# BOB_v0_6.net
KiCad netlist of a schematic drawn in EAGLE
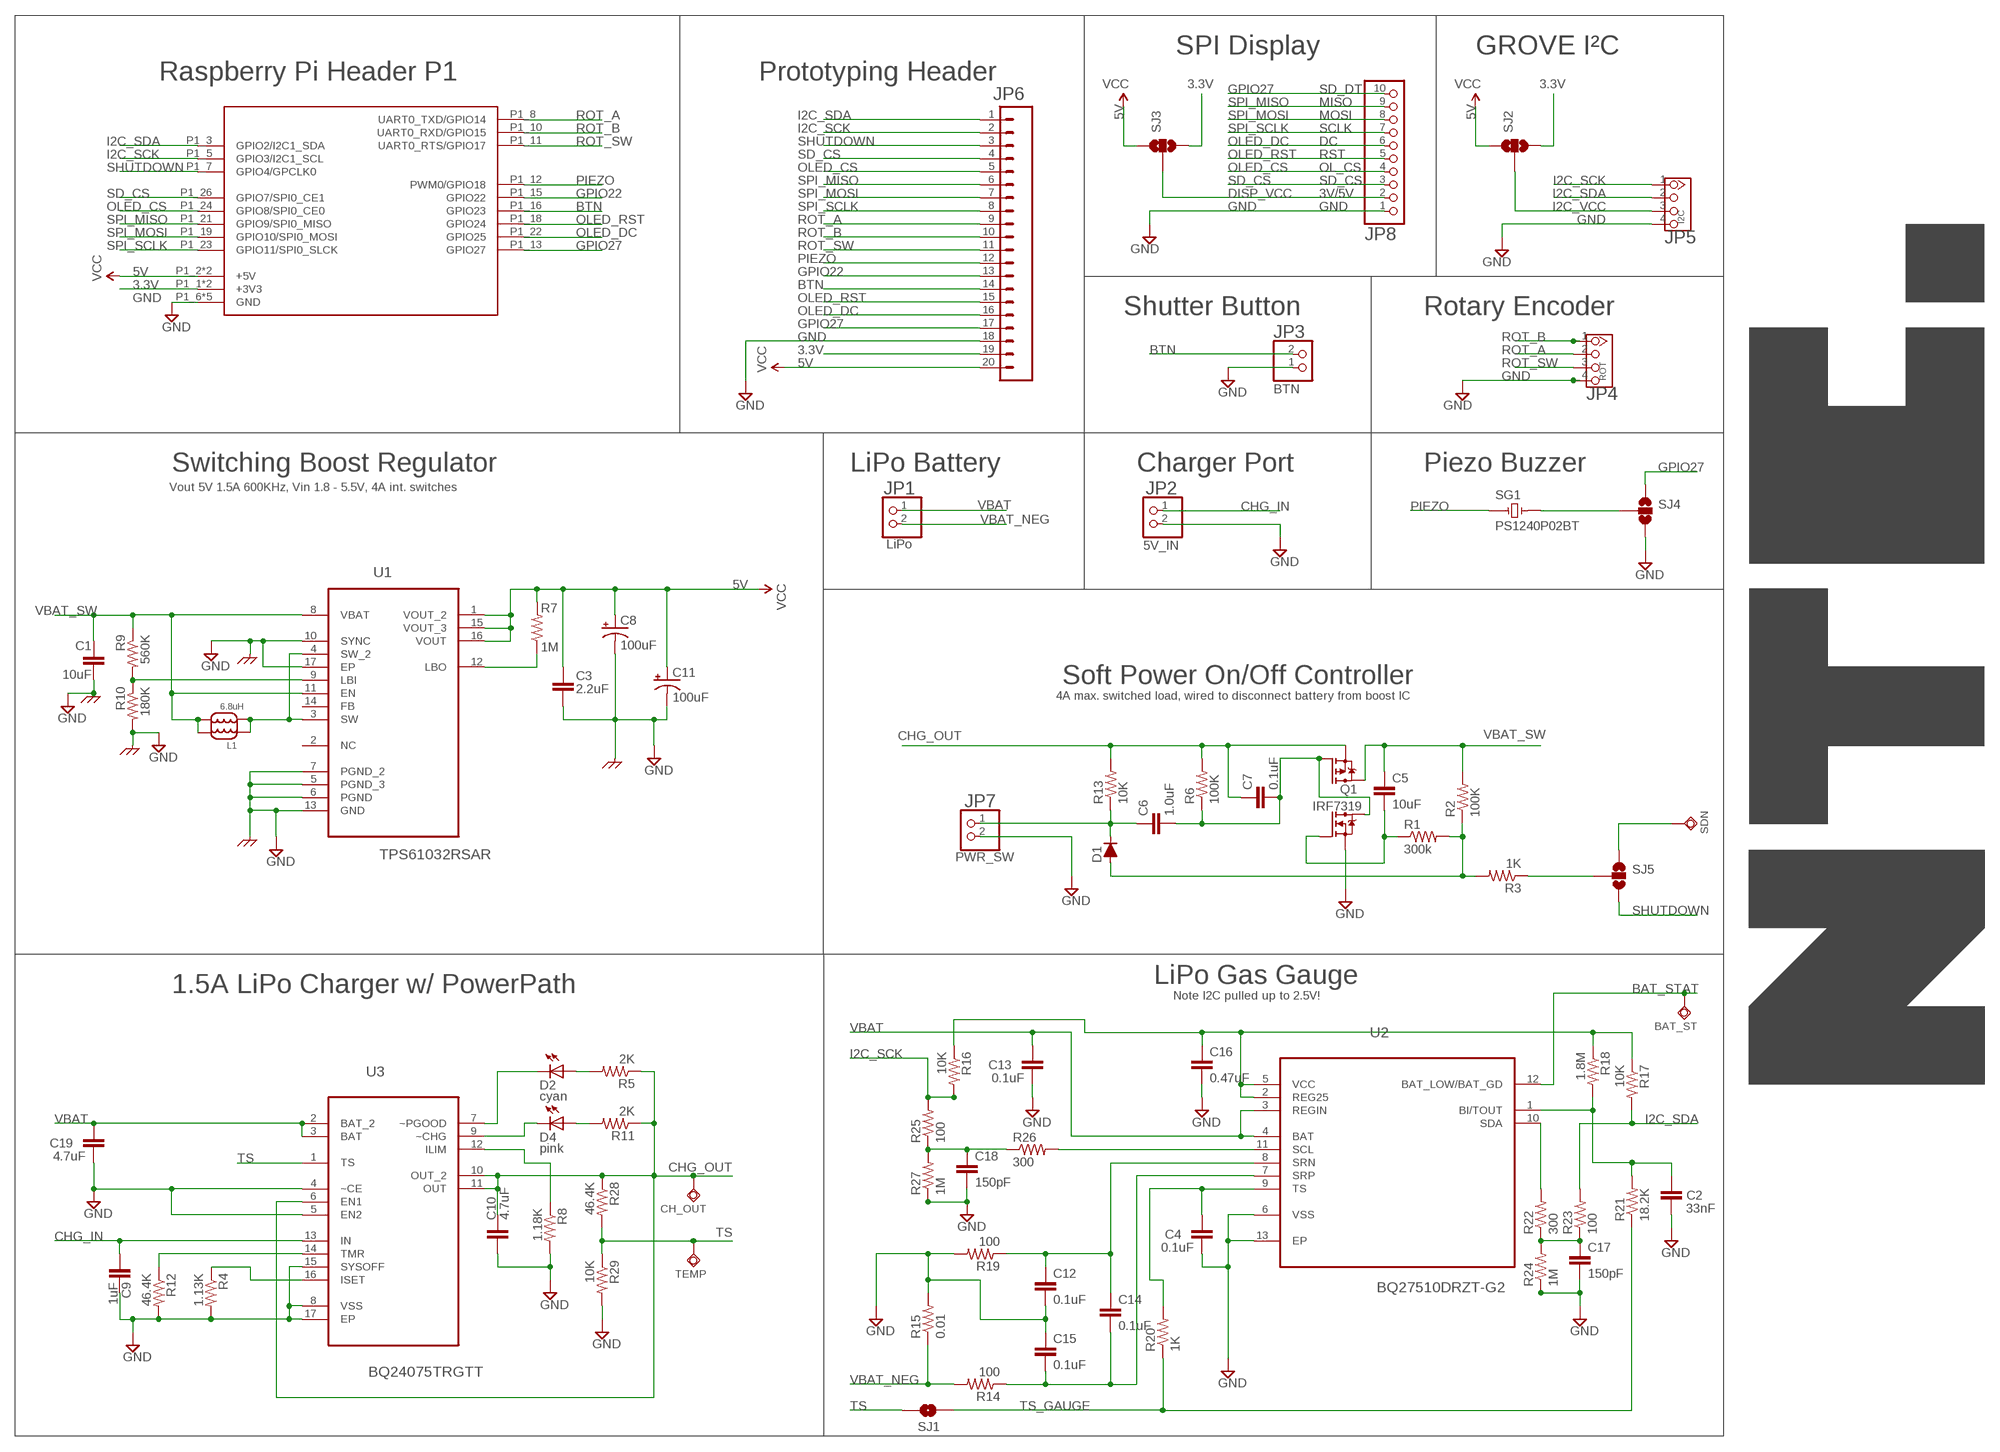
[diagram p0: schematic, sheet 1]

(export (version "E")
  (design (tool "Eeschema 10.0.6"))
  (components
    (comp (ref "BAT_ST")
      (value "TP1.2")
      (footprint "eagle-import:TP_1.2")
      (libsource (lib "eagle-import") (part "TP1.2"))
    )
    (comp (ref "C1")
      (value "10uF")
      (footprint "eagle-import:1206")
      (libsource (lib "eagle-import") (part "CAP1206"))
    )
    (comp (ref "C2")
      (value "33nF")
      (footprint "eagle-import:0603-CAP")
      (libsource (lib "eagle-import") (part "CAP0603-CAP"))
    )
    (comp (ref "C3")
      (value "2.2uF")
      (footprint "eagle-import:0603")
      (libsource (lib "eagle-import") (part "CAP0603"))
    )
    (comp (ref "C4")
      (value "0.1uF")
      (footprint "eagle-import:0603-CAP")
      (libsource (lib "eagle-import") (part "CAP0603-CAP"))
    )
    (comp (ref "C5")
      (value "10uF")
      (footprint "eagle-import:0603-CAP")
      (libsource (lib "eagle-import") (part "10UF-6.3V-20%(0603)"))
    )
    (comp (ref "C6")
      (value "1.0uF")
      (footprint "eagle-import:0603-CAP")
      (libsource (lib "eagle-import") (part "1.0UF-16V-10%(0603)"))
    )
    (comp (ref "C7")
      (value "0.1uF")
      (footprint "eagle-import:0603-CAP")
      (libsource (lib "eagle-import") (part "0.1UF-25V-5%(0603)"))
    )
    (comp (ref "C8")
      (value "100uF")
      (footprint "eagle-import:EIA3216")
      (libsource (lib "eagle-import") (part "CAP_POL1206"))
    )
    (comp (ref "C9")
      (value "1uF")
      (footprint "eagle-import:0603-CAP")
      (libsource (lib "eagle-import") (part "CAP0603-CAP"))
    )
    (comp (ref "C10")
      (value "4.7uF")
      (footprint "eagle-import:0603-CAP")
      (libsource (lib "eagle-import") (part "CAP0603-CAP"))
    )
    (comp (ref "C11")
      (value "100uF")
      (footprint "eagle-import:EIA3216")
      (libsource (lib "eagle-import") (part "CAP_POL1206"))
    )
    (comp (ref "C12")
      (value "0.1uF")
      (footprint "eagle-import:0603-CAP")
      (libsource (lib "eagle-import") (part "SparkFun-Capacitors_CAP0603-CAP"))
    )
    (comp (ref "C13")
      (value "0.1uF")
      (footprint "eagle-import:0603-CAP")
      (libsource (lib "eagle-import") (part "CAP0603-CAP"))
    )
    (comp (ref "C14")
      (value "0.1uF")
      (footprint "eagle-import:0603-CAP")
      (libsource (lib "eagle-import") (part "SparkFun-Capacitors_CAP0603-CAP"))
    )
    (comp (ref "C15")
      (value "0.1uF")
      (footprint "eagle-import:0603-CAP")
      (libsource (lib "eagle-import") (part "SparkFun-Capacitors_CAP0603-CAP"))
    )
    (comp (ref "C16")
      (value "0.47uF")
      (footprint "eagle-import:0603-CAP")
      (libsource (lib "eagle-import") (part "SparkFun-Capacitors_CAP0603-CAP"))
    )
    (comp (ref "C17")
      (value "150pF")
      (footprint "eagle-import:0603-CAP")
      (libsource (lib "eagle-import") (part "SparkFun-Capacitors_CAP0603-CAP"))
    )
    (comp (ref "C18")
      (value "150pF")
      (footprint "eagle-import:0603-CAP")
      (libsource (lib "eagle-import") (part "SparkFun-Capacitors_CAP0603-CAP"))
    )
    (comp (ref "C19")
      (value "4.7uF")
      (footprint "eagle-import:0603-CAP")
      (libsource (lib "eagle-import") (part "CAP0603-CAP"))
    )
    (comp (ref "CH_OUT")
      (value "TP1.2")
      (footprint "eagle-import:TP_1.2")
      (libsource (lib "eagle-import") (part "TP1.2"))
    )
    (comp (ref "D1")
      (value "D-FILL-SMB")
      (footprint "eagle-import:SMB")
      (libsource (lib "eagle-import") (part "D-FILL-SMB"))
    )
    (comp (ref "D2")
      (value "cyan")
      (footprint "eagle-import:LED-0603")
      (libsource (lib "eagle-import") (part "LED0603"))
    )
    (comp (ref "D4")
      (value "pink")
      (footprint "eagle-import:LED-0603")
      (libsource (lib "eagle-import") (part "LED0603"))
    )
    (comp (ref "JP1")
      (value "LiPo")
      (footprint "eagle-import:JST-PH-2-THM")
      (libsource (lib "eagle-import") (part "JST_2PIN-THM"))
    )
    (comp (ref "JP2")
      (value "5V_IN")
      (footprint "eagle-import:JST-PH-2-THM")
      (libsource (lib "eagle-import") (part "JST_2PIN-THM"))
    )
    (comp (ref "JP3")
      (value "BTN")
      (footprint "eagle-import:JST-PH-2-THM")
      (libsource (lib "eagle-import") (part "JST_2PIN-THM"))
    )
    (comp (ref "JP4")
      (value "ROT")
      (footprint "eagle-import:4P-2.0")
      (libsource (lib "eagle-import") (part "TWIG-4P-2.0-2.0"))
    )
    (comp (ref "JP5")
      (value "I2C")
      (footprint "eagle-import:4P-2.0")
      (libsource (lib "eagle-import") (part "TWIG-4P-2.0-2.0"))
    )
    (comp (ref "JP6")
      (value "M20LOCK_LONGPADS")
      (footprint "eagle-import:1X20_LOCK_LONGPADS")
      (libsource (lib "eagle-import") (part "M20LOCK_LONGPADS"))
    )
    (comp (ref "JP7")
      (value "PWR_SW")
      (footprint "eagle-import:JST-PH-2-THM")
      (libsource (lib "eagle-import") (part "JST_2PIN-THM"))
    )
    (comp (ref "JP8")
      (value "PINHD-1X10")
      (footprint "eagle-import:1X10-BIG")
      (libsource (lib "eagle-import") (part "PINHD-1X10"))
    )
    (comp (ref "L1")
      (value "6.8uH")
      (footprint "eagle-import:SUMIDA_CDRH124")
      (libsource (lib "eagle-import") (part "SUMIDA_CDRH124CDRH124NP-6R8MC"))
    )
    (comp (ref "PICAM_SHIELD")
      (value "PICAM_RPI-B-PICAM")
      (footprint "eagle-import:PICAM_RPI-B-PICAM")
      (libsource (lib "eagle-import") (part "PICAM_RPI-B-PICAM"))
    )
    (comp (ref "Q1")
      (value "IRF7319")
      (footprint "eagle-import:SO08-IRF")
      (libsource (lib "eagle-import") (part "IRF7319Q"))
    )
    (comp (ref "R1")
      (value "300k")
      (footprint "eagle-import:0603-RES")
      (libsource (lib "eagle-import") (part "SparkFun-Passives_RESISTOR0603-RES"))
    )
    (comp (ref "R2")
      (value "100K")
      (footprint "eagle-import:0603-RES")
      (libsource (lib "eagle-import") (part "SparkFun-Passives_RESISTOR0603-RES"))
    )
    (comp (ref "R3")
      (value "1K")
      (footprint "eagle-import:0603-RES")
      (libsource (lib "eagle-import") (part "SparkFun-Passives_RESISTOR0603-RES"))
    )
    (comp (ref "R4")
      (value "1.13K")
      (footprint "eagle-import:0603-RES")
      (libsource (lib "eagle-import") (part "RESISTOR0603-RES"))
    )
    (comp (ref "R5")
      (value "2K")
      (footprint "eagle-import:0603-RES")
      (libsource (lib "eagle-import") (part "RESISTOR0603-RES"))
    )
    (comp (ref "R6")
      (value "100K")
      (footprint "eagle-import:0603-RES")
      (libsource (lib "eagle-import") (part "SparkFun-Passives_RESISTOR0603-RES"))
    )
    (comp (ref "R7")
      (value "1M")
      (footprint "eagle-import:0603-RES")
      (libsource (lib "eagle-import") (part "RESISTOR0603-RES"))
    )
    (comp (ref "R8")
      (value "1.18K")
      (footprint "eagle-import:0603-RES")
      (libsource (lib "eagle-import") (part "RESISTOR0603-RES"))
    )
    (comp (ref "R9")
      (value "560K")
      (footprint "eagle-import:0603-RES")
      (libsource (lib "eagle-import") (part "RESISTOR0603-RES"))
    )
    (comp (ref "R10")
      (value "180K")
      (footprint "eagle-import:0603-RES")
      (libsource (lib "eagle-import") (part "RESISTOR0603-RES"))
    )
    (comp (ref "R11")
      (value "2K")
      (footprint "eagle-import:0603-RES")
      (libsource (lib "eagle-import") (part "RESISTOR0603-RES"))
    )
    (comp (ref "R12")
      (value "46.4K")
      (footprint "eagle-import:0603-RES")
      (libsource (lib "eagle-import") (part "RESISTOR0603-RES"))
    )
    (comp (ref "R13")
      (value "10K")
      (footprint "eagle-import:0603-RES")
      (libsource (lib "eagle-import") (part "SparkFun-Passives_RESISTOR0603-RES"))
    )
    (comp (ref "R14")
      (value "100")
      (footprint "eagle-import:0603-RES")
      (libsource (lib "eagle-import") (part "RESISTOR0603-RES"))
    )
    (comp (ref "R15")
      (value "0.01")
      (footprint "eagle-import:0603-RES")
      (libsource (lib "eagle-import") (part "SparkFun-Passives_RESISTOR0603-RES"))
    )
    (comp (ref "R16")
      (value "10K")
      (footprint "eagle-import:0603-RES")
      (libsource (lib "eagle-import") (part "RESISTOR0603-RES"))
    )
    (comp (ref "R17")
      (value "10K")
      (footprint "eagle-import:0603-RES")
      (libsource (lib "eagle-import") (part "RESISTOR0603-RES"))
    )
    (comp (ref "R18")
      (value "1.8M")
      (footprint "eagle-import:0603-RES")
      (libsource (lib "eagle-import") (part "RESISTOR0603-RES"))
    )
    (comp (ref "R19")
      (value "100")
      (footprint "eagle-import:0603-RES")
      (libsource (lib "eagle-import") (part "RESISTOR0603-RES"))
    )
    (comp (ref "R20")
      (value "1K")
      (footprint "eagle-import:0603-RES")
      (libsource (lib "eagle-import") (part "SparkFun-Resistors_RESISTOR0603-RES"))
    )
    (comp (ref "R21")
      (value "18.2K")
      (footprint "eagle-import:0603-RES")
      (libsource (lib "eagle-import") (part "SparkFun-Resistors_RESISTOR0603-RES"))
    )
    (comp (ref "R22")
      (value "300")
      (footprint "eagle-import:0603-RES")
      (libsource (lib "eagle-import") (part "SparkFun-Resistors_RESISTOR0603-RES"))
    )
    (comp (ref "R23")
      (value "100")
      (footprint "eagle-import:0603-RES")
      (libsource (lib "eagle-import") (part "SparkFun-Resistors_RESISTOR0603-RES"))
    )
    (comp (ref "R24")
      (value "1M")
      (footprint "eagle-import:0603-RES")
      (libsource (lib "eagle-import") (part "SparkFun-Resistors_RESISTOR0603-RES"))
    )
    (comp (ref "R25")
      (value "100")
      (footprint "eagle-import:0603-RES")
      (libsource (lib "eagle-import") (part "SparkFun-Resistors_RESISTOR0603-RES"))
    )
    (comp (ref "R26")
      (value "300")
      (footprint "eagle-import:0603-RES")
      (libsource (lib "eagle-import") (part "SparkFun-Resistors_RESISTOR0603-RES"))
    )
    (comp (ref "R27")
      (value "1M")
      (footprint "eagle-import:0603-RES")
      (libsource (lib "eagle-import") (part "SparkFun-Resistors_RESISTOR0603-RES"))
    )
    (comp (ref "R28")
      (value "46.4K")
      (footprint "eagle-import:0603-RES")
      (libsource (lib "eagle-import") (part "RESISTOR0603-RES"))
    )
    (comp (ref "R29")
      (value "10K")
      (footprint "eagle-import:0603-RES")
      (libsource (lib "eagle-import") (part "RESISTOR0603-RES"))
    )
    (comp (ref "SDN")
      (value "TP1.2")
      (footprint "eagle-import:TP_1.2")
      (libsource (lib "eagle-import") (part "TP1.2"))
    )
    (comp (ref "SG1")
      (value "PS1240P02BT")
      (footprint "eagle-import:PS1240")
      (libsource (lib "eagle-import") (part "PS1240P02BT"))
    )
    (comp (ref "SJ1")
      (value "SOLDERJUMPER-OLDTRACE")
      (footprint "eagle-import:SJ_2S-TRACE")
      (libsource (lib "eagle-import") (part "SOLDERJUMPER-OLDTRACE"))
    )
    (comp (ref "SJ2")
      (value "SOLDERJUMPER_2WAYPASTE1&2")
      (footprint "eagle-import:SJ_3_PASTE1&2")
      (libsource (lib "eagle-import") (part "SOLDERJUMPER_2WAYPASTE1&2"))
    )
    (comp (ref "SJ3")
      (value "SOLDERJUMPER_2WAYPASTE2&3")
      (footprint "eagle-import:SJ_3_PASTE2&3")
      (libsource (lib "eagle-import") (part "SOLDERJUMPER_2WAYPASTE2&3"))
    )
    (comp (ref "SJ4")
      (value "SOLDERJUMPER_2WAYPASTE1&2")
      (footprint "eagle-import:SJ_3_PASTE1&2")
      (libsource (lib "eagle-import") (part "SOLDERJUMPER_2WAYPASTE1&2"))
    )
    (comp (ref "SJ5")
      (value "SOLDERJUMPER_2WAYPASTE2&3")
      (footprint "eagle-import:SJ_3_PASTE2&3")
      (libsource (lib "eagle-import") (part "SOLDERJUMPER_2WAYPASTE2&3"))
    )
    (comp (ref "TEMP")
      (value "TP1.2")
      (footprint "eagle-import:TP_1.2")
      (libsource (lib "eagle-import") (part "TP1.2"))
    )
    (comp (ref "U1")
      (value "TPS61032RSAR")
      (footprint "eagle-import:QFN65P400X400X100-17N")
      (libsource (lib "eagle-import") (part "TPS61032RSAR"))
    )
    (comp (ref "U2")
      (value "BQ27510DRZT-G2")
      (footprint "eagle-import:SON40P400X250X100-13N")
      (libsource (lib "eagle-import") (part "BQ27510DRZT-G2"))
    )
    (comp (ref "U3")
      (value "BQ24075TRGTT")
      (footprint "eagle-import:QFN50P300X300X100-17N")
      (libsource (lib "eagle-import") (part "BQ24075TRGTT"))
    )
  )
  (nets
    (net (code "1") (name "3.3V") (class "Default")
      (node (ref "JP6") (pin "19") (pinfunction "19_19") (pintype "passive"))
      (node (ref "PICAM_SHIELD") (pin "P1_1") (pinfunction "+3V3_P1_1") (pintype "power_in"))
      (node (ref "PICAM_SHIELD") (pin "P1_17") (pinfunction "+3V3_P1_17") (pintype "power_in"))
      (node (ref "SJ2") (pin "3") (pinfunction "3_3") (pintype "passive"))
      (node (ref "SJ3") (pin "3") (pinfunction "3_3") (pintype "passive"))
    )
    (net (code "2") (name "5V") (class "Default")
      (node (ref "C11") (pin "A") (pinfunction "+_A") (pintype "passive"))
      (node (ref "C3") (pin "1") (pinfunction "1_1") (pintype "passive"))
      (node (ref "C8") (pin "A") (pinfunction "+_A") (pintype "passive"))
      (node (ref "JP6") (pin "20") (pinfunction "20_20") (pintype "passive"))
      (node (ref "PICAM_SHIELD") (pin "P1_2") (pinfunction "+5V_P1_2") (pintype "power_in"))
      (node (ref "PICAM_SHIELD") (pin "P1_4") (pinfunction "+5V_P1_4") (pintype "power_in"))
      (node (ref "R7") (pin "2") (pinfunction "2_2") (pintype "passive"))
      (node (ref "SJ2") (pin "1") (pinfunction "1_1") (pintype "passive"))
      (node (ref "SJ3") (pin "1") (pinfunction "1_1") (pintype "passive"))
      (node (ref "U1") (pin "1") (pinfunction "VOUT_2_1") (pintype "output"))
      (node (ref "U1") (pin "15") (pinfunction "VOUT_3_15") (pintype "output"))
      (node (ref "U1") (pin "16") (pinfunction "VOUT_16") (pintype "output"))
    )
    (net (code "3") (name "BAT_STAT") (class "Default")
      (node (ref "BAT_ST") (pin "1") (pinfunction "TP_1") (pintype "passive"))
      (node (ref "U2") (pin "12") (pinfunction "BAT_LOW/BAT_GD_12") (pintype "output"))
    )
    (net (code "4") (name "BTN") (class "Default")
      (node (ref "JP3") (pin "2") (pinfunction "1_2") (pintype "passive"))
      (node (ref "JP6") (pin "14") (pinfunction "14_14") (pintype "passive"))
      (node (ref "PICAM_SHIELD") (pin "P1_16") (pinfunction "GPIO23_P1_16") (pintype "bidirectional"))
    )
    (net (code "5") (name "CHG_IN") (class "Default")
      (node (ref "C9") (pin "1") (pinfunction "1_1") (pintype "passive"))
      (node (ref "JP2") (pin "1") (pinfunction "2_1") (pintype "passive"))
      (node (ref "U3") (pin "13") (pinfunction "IN_13") (pintype "input"))
    )
    (net (code "6") (name "CHG_OUT") (class "Default")
      (node (ref "C10") (pin "1") (pinfunction "1_1") (pintype "passive"))
      (node (ref "C7") (pin "1") (pinfunction "1_1") (pintype "passive"))
      (node (ref "CH_OUT") (pin "1") (pinfunction "TP_1") (pintype "passive"))
      (node (ref "Q1") (pin "3") (pinfunction "P-S2_3") (pintype "passive"))
      (node (ref "R11") (pin "1") (pinfunction "1_1") (pintype "passive"))
      (node (ref "R13") (pin "2") (pinfunction "2_2") (pintype "passive"))
      (node (ref "R28") (pin "1") (pinfunction "1_1") (pintype "passive"))
      (node (ref "R5") (pin "1") (pinfunction "1_1") (pintype "passive"))
      (node (ref "R6") (pin "2") (pinfunction "2_2") (pintype "passive"))
      (node (ref "U3") (pin "10") (pinfunction "OUT_2_10") (pintype "output"))
      (node (ref "U3") (pin "11") (pinfunction "OUT_11") (pintype "output"))
      (node (ref "U3") (pin "6") (pinfunction "EN1_6") (pintype "input"))
    )
    (net (code "7") (name "DISP_VCC") (class "Default")
      (node (ref "JP8") (pin "2") (pinfunction "2_2") (pintype "passive"))
      (node (ref "SJ3") (pin "2") (pinfunction "2_2") (pintype "passive"))
    )
    (net (code "8") (name "GND") (class "Default")
      (node (ref "C1") (pin "2") (pinfunction "2_2") (pintype "passive"))
      (node (ref "C10") (pin "2") (pinfunction "2_2") (pintype "passive"))
      (node (ref "C11") (pin "C") (pinfunction "-_C") (pintype "passive"))
      (node (ref "C12") (pin "2") (pinfunction "2_2") (pintype "passive"))
      (node (ref "C13") (pin "2") (pinfunction "2_2") (pintype "passive"))
      (node (ref "C15") (pin "1") (pinfunction "1_1") (pintype "passive"))
      (node (ref "C16") (pin "2") (pinfunction "2_2") (pintype "passive"))
      (node (ref "C17") (pin "2") (pinfunction "2_2") (pintype "passive"))
      (node (ref "C18") (pin "2") (pinfunction "2_2") (pintype "passive"))
      (node (ref "C19") (pin "2") (pinfunction "2_2") (pintype "passive"))
      (node (ref "C2") (pin "2") (pinfunction "2_2") (pintype "passive"))
      (node (ref "C3") (pin "2") (pinfunction "2_2") (pintype "passive"))
      (node (ref "C4") (pin "2") (pinfunction "2_2") (pintype "passive"))
      (node (ref "C8") (pin "C") (pinfunction "-_C") (pintype "passive"))
      (node (ref "C9") (pin "2") (pinfunction "2_2") (pintype "passive"))
      (node (ref "JP2") (pin "2") (pinfunction "1_2") (pintype "passive"))
      (node (ref "JP3") (pin "1") (pinfunction "2_1") (pintype "passive"))
      (node (ref "JP4") (pin "4") (pinfunction "4_4") (pintype "bidirectional"))
      (node (ref "JP5") (pin "4") (pinfunction "4_4") (pintype "bidirectional"))
      (node (ref "JP6") (pin "18") (pinfunction "18_18") (pintype "passive"))
      (node (ref "JP7") (pin "2") (pinfunction "1_2") (pintype "passive"))
      (node (ref "JP8") (pin "1") (pinfunction "1_1") (pintype "passive"))
      (node (ref "PICAM_SHIELD") (pin "P1_14") (pinfunction "GND_P1_14") (pintype "power_in"))
      (node (ref "PICAM_SHIELD") (pin "P1_20") (pinfunction "GND_P1_20") (pintype "power_in"))
      (node (ref "PICAM_SHIELD") (pin "P1_25") (pinfunction "GND_P1_25") (pintype "power_in"))
      (node (ref "PICAM_SHIELD") (pin "P1_6") (pinfunction "GND_P1_6") (pintype "power_in"))
      (node (ref "PICAM_SHIELD") (pin "P1_9") (pinfunction "GND_P1_9") (pintype "power_in"))
      (node (ref "Q1") (pin "1") (pinfunction "N-S1_1") (pintype "passive"))
      (node (ref "R10") (pin "2") (pinfunction "2_2") (pintype "passive"))
      (node (ref "R12") (pin "2") (pinfunction "2_2") (pintype "passive"))
      (node (ref "R15") (pin "2") (pinfunction "2_2") (pintype "passive"))
      (node (ref "R19") (pin "2") (pinfunction "2_2") (pintype "passive"))
      (node (ref "R24") (pin "1") (pinfunction "1_1") (pintype "passive"))
      (node (ref "R27") (pin "1") (pinfunction "1_1") (pintype "passive"))
      (node (ref "R29") (pin "2") (pinfunction "2_2") (pintype "passive"))
      (node (ref "R4") (pin "2") (pinfunction "2_2") (pintype "passive"))
      (node (ref "R8") (pin "2") (pinfunction "2_2") (pintype "passive"))
      (node (ref "SJ4") (pin "3") (pinfunction "3_3") (pintype "passive"))
      (node (ref "U1") (pin "10") (pinfunction "SYNC_10") (pintype "input"))
      (node (ref "U1") (pin "13") (pinfunction "GND_13") (pintype "passive"))
      (node (ref "U1") (pin "17") (pinfunction "EP_17") (pintype "passive"))
      (node (ref "U1") (pin "5") (pinfunction "PGND_3_5") (pintype "passive"))
      (node (ref "U1") (pin "6") (pinfunction "PGND_6") (pintype "passive"))
      (node (ref "U1") (pin "7") (pinfunction "PGND_2_7") (pintype "passive"))
      (node (ref "U2") (pin "13") (pinfunction "EP_13") (pintype "passive"))
      (node (ref "U2") (pin "6") (pinfunction "VSS_6") (pintype "power_in"))
      (node (ref "U3") (pin "15") (pinfunction "SYSOFF_15") (pintype "input"))
      (node (ref "U3") (pin "17") (pinfunction "EP_17") (pintype "passive"))
      (node (ref "U3") (pin "4") (pinfunction "~{CE}_4") (pintype "input"))
      (node (ref "U3") (pin "5") (pinfunction "EN2_5") (pintype "input"))
      (node (ref "U3") (pin "8") (pinfunction "VSS_8") (pintype "passive"))
    )
    (net (code "9") (name "GPIO22") (class "Default")
      (node (ref "JP6") (pin "13") (pinfunction "13_13") (pintype "passive"))
      (node (ref "PICAM_SHIELD") (pin "P1_15") (pinfunction "GPIO22_P1_15") (pintype "bidirectional"))
    )
    (net (code "10") (name "GPIO27") (class "Default")
      (node (ref "JP6") (pin "17") (pinfunction "17_17") (pintype "passive"))
      (node (ref "JP8") (pin "10") (pinfunction "10_10") (pintype "passive"))
      (node (ref "PICAM_SHIELD") (pin "P1_13") (pinfunction "GPIO27_P1_13") (pintype "bidirectional"))
      (node (ref "SJ4") (pin "1") (pinfunction "1_1") (pintype "passive"))
    )
    (net (code "11") (name "I2C_SCK") (class "Default")
      (node (ref "JP5") (pin "1") (pinfunction "1_1") (pintype "bidirectional"))
      (node (ref "JP6") (pin "2") (pinfunction "2_2") (pintype "passive"))
      (node (ref "PICAM_SHIELD") (pin "P1_5") (pinfunction "GPIO3/I2C1_SCL_P1_5") (pintype "bidirectional"))
      (node (ref "R16") (pin "2") (pinfunction "2_2") (pintype "passive"))
      (node (ref "R25") (pin "2") (pinfunction "2_2") (pintype "passive"))
    )
    (net (code "12") (name "I2C_SDA") (class "Default")
      (node (ref "JP5") (pin "2") (pinfunction "2_2") (pintype "bidirectional"))
      (node (ref "JP6") (pin "1") (pinfunction "1_1") (pintype "passive"))
      (node (ref "PICAM_SHIELD") (pin "P1_3") (pinfunction "GPIO2/I2C1_SDA_P1_3") (pintype "bidirectional"))
      (node (ref "R17") (pin "2") (pinfunction "2_2") (pintype "passive"))
      (node (ref "R23") (pin "2") (pinfunction "2_2") (pintype "passive"))
    )
    (net (code "13") (name "I2C_VCC") (class "Default")
      (node (ref "JP5") (pin "3") (pinfunction "3_3") (pintype "bidirectional"))
      (node (ref "SJ2") (pin "2") (pinfunction "2_2") (pintype "passive"))
    )
    (net (code "14") (name "Net-(C17-Pad1)") (class "Default")
      (node (ref "C17") (pin "1") (pinfunction "1_1") (pintype "passive"))
      (node (ref "R22") (pin "1") (pinfunction "1_1") (pintype "passive"))
      (node (ref "R23") (pin "1") (pinfunction "1_1") (pintype "passive"))
      (node (ref "R24") (pin "2") (pinfunction "2_2") (pintype "passive"))
    )
    (net (code "15") (name "Net-(C18-Pad1)") (class "Default")
      (node (ref "C18") (pin "1") (pinfunction "1_1") (pintype "passive"))
      (node (ref "R25") (pin "1") (pinfunction "1_1") (pintype "passive"))
      (node (ref "R26") (pin "1") (pinfunction "1_1") (pintype "passive"))
      (node (ref "R27") (pin "2") (pinfunction "2_2") (pintype "passive"))
    )
    (net (code "16") (name "Net-(D1-A)") (class "Default")
      (node (ref "D1") (pin "2") (pinfunction "A_2") (pintype "passive"))
      (node (ref "R1") (pin "2") (pinfunction "2_2") (pintype "passive"))
      (node (ref "R2") (pin "1") (pinfunction "1_1") (pintype "passive"))
      (node (ref "R3") (pin "2") (pinfunction "2_2") (pintype "passive"))
    )
    (net (code "17") (name "Net-(D1-C)") (class "Default")
      (node (ref "C6") (pin "1") (pinfunction "1_1") (pintype "passive"))
      (node (ref "D1") (pin "1") (pinfunction "C_1") (pintype "passive"))
      (node (ref "JP7") (pin "1") (pinfunction "2_1") (pintype "passive"))
      (node (ref "R13") (pin "1") (pinfunction "1_1") (pintype "passive"))
    )
    (net (code "18") (name "Net-(D2-PadA)") (class "Default")
      (node (ref "D2") (pin "A") (pinfunction "A_A") (pintype "passive"))
      (node (ref "R5") (pin "2") (pinfunction "2_2") (pintype "passive"))
    )
    (net (code "19") (name "Net-(D4-PadA)") (class "Default")
      (node (ref "D4") (pin "A") (pinfunction "A_A") (pintype "passive"))
      (node (ref "R11") (pin "2") (pinfunction "2_2") (pintype "passive"))
    )
    (net (code "20") (name "Net-(Q1-N-G1)") (class "Default")
      (node (ref "C5") (pin "2") (pinfunction "2_2") (pintype "passive"))
      (node (ref "Q1") (pin "2") (pinfunction "N-G1_2") (pintype "passive"))
      (node (ref "R1") (pin "1") (pinfunction "1_1") (pintype "passive"))
    )
    (net (code "21") (name "Net-(Q1-P-G2)") (class "Default")
      (node (ref "C6") (pin "2") (pinfunction "2_2") (pintype "passive"))
      (node (ref "C7") (pin "2") (pinfunction "2_2") (pintype "passive"))
      (node (ref "Q1") (pin "4") (pinfunction "P-G2_4") (pintype "passive"))
      (node (ref "Q1") (pin "7") (pinfunction "N-D1_7") (pintype "passive"))
      (node (ref "Q1") (pin "8") (pinfunction "N-D1_8") (pintype "passive"))
      (node (ref "R6") (pin "1") (pinfunction "1_1") (pintype "passive"))
    )
    (net (code "22") (name "Net-(R3-Pad1)") (class "Default")
      (node (ref "R3") (pin "1") (pinfunction "1_1") (pintype "passive"))
      (node (ref "SJ5") (pin "2") (pinfunction "2_2") (pintype "passive"))
    )
    (net (code "23") (name "Net-(SDN-TP)") (class "Default")
      (node (ref "SDN") (pin "1") (pinfunction "TP_1") (pintype "passive"))
      (node (ref "SJ5") (pin "1") (pinfunction "1_1") (pintype "passive"))
    )
    (net (code "24") (name "Net-(SG1-2)") (class "Default")
      (node (ref "SG1") (pin "P$2") (pinfunction "2_P$2") (pintype "passive"))
      (node (ref "SJ4") (pin "2") (pinfunction "2_2") (pintype "passive"))
    )
    (net (code "25") (name "Net-(U1-LBI)") (class "Default")
      (node (ref "R10") (pin "1") (pinfunction "1_1") (pintype "passive"))
      (node (ref "R9") (pin "2") (pinfunction "2_2") (pintype "passive"))
      (node (ref "U1") (pin "9") (pinfunction "LBI_9") (pintype "input"))
    )
    (net (code "26") (name "Net-(U1-LBO)") (class "Default")
      (node (ref "R7") (pin "1") (pinfunction "1_1") (pintype "passive"))
      (node (ref "U1") (pin "12") (pinfunction "LBO_12") (pintype "output"))
    )
    (net (code "27") (name "Net-(U1-SW)") (class "Default")
      (node (ref "L1") (pin "P$3") (pinfunction "2_P$3") (pintype "passive"))
      (node (ref "L1") (pin "P$4") (pinfunction "2_P$4") (pintype "passive"))
      (node (ref "U1") (pin "3") (pinfunction "SW_3") (pintype "input"))
      (node (ref "U1") (pin "4") (pinfunction "SW_2_4") (pintype "input"))
    )
    (net (code "28") (name "Net-(U2-BI{slash}TOUT)") (class "Default")
      (node (ref "C2") (pin "1") (pinfunction "1_1") (pintype "passive"))
      (node (ref "R18") (pin "2") (pinfunction "2_2") (pintype "passive"))
      (node (ref "R21") (pin "2") (pinfunction "2_2") (pintype "passive"))
      (node (ref "U2") (pin "1") (pinfunction "BI/TOUT_1") (pintype "bidirectional"))
    )
    (net (code "29") (name "Net-(U2-REG25)") (class "Default")
      (node (ref "C16") (pin "1") (pinfunction "1_1") (pintype "passive"))
      (node (ref "R16") (pin "1") (pinfunction "1_1") (pintype "passive"))
      (node (ref "R17") (pin "1") (pinfunction "1_1") (pintype "passive"))
      (node (ref "R18") (pin "1") (pinfunction "1_1") (pintype "passive"))
      (node (ref "U2") (pin "2") (pinfunction "REG25_2") (pintype "power_in"))
      (node (ref "U2") (pin "5") (pinfunction "VCC_5") (pintype "power_in"))
    )
    (net (code "30") (name "Net-(U2-SCL)") (class "Default")
      (node (ref "R26") (pin "2") (pinfunction "2_2") (pintype "passive"))
      (node (ref "U2") (pin "11") (pinfunction "SCL_11") (pintype "input"))
    )
    (net (code "31") (name "Net-(U2-SDA)") (class "Default")
      (node (ref "R22") (pin "2") (pinfunction "2_2") (pintype "passive"))
      (node (ref "U2") (pin "10") (pinfunction "SDA_10") (pintype "bidirectional"))
    )
    (net (code "32") (name "Net-(U2-SRN)") (class "Default")
      (node (ref "C12") (pin "1") (pinfunction "1_1") (pintype "passive"))
      (node (ref "C14") (pin "1") (pinfunction "1_1") (pintype "passive"))
      (node (ref "R19") (pin "1") (pinfunction "1_1") (pintype "passive"))
      (node (ref "U2") (pin "8") (pinfunction "SRN_8") (pintype "input"))
    )
    (net (code "33") (name "Net-(U2-SRP)") (class "Default")
      (node (ref "C14") (pin "2") (pinfunction "2_2") (pintype "passive"))
      (node (ref "C15") (pin "2") (pinfunction "2_2") (pintype "passive"))
      (node (ref "R14") (pin "1") (pinfunction "1_1") (pintype "passive"))
      (node (ref "U2") (pin "7") (pinfunction "SRP_7") (pintype "input"))
    )
    (net (code "34") (name "Net-(U2-TS)") (class "Default")
      (node (ref "C4") (pin "1") (pinfunction "1_1") (pintype "passive"))
      (node (ref "R20") (pin "2") (pinfunction "2_2") (pintype "passive"))
      (node (ref "U2") (pin "9") (pinfunction "TS_9") (pintype "input"))
    )
    (net (code "35") (name "Net-(U3-ILIM)") (class "Default")
      (node (ref "R8") (pin "1") (pinfunction "1_1") (pintype "passive"))
      (node (ref "U3") (pin "12") (pinfunction "ILIM_12") (pintype "output"))
    )
    (net (code "36") (name "Net-(U3-ISET)") (class "Default")
      (node (ref "R4") (pin "1") (pinfunction "1_1") (pintype "passive"))
      (node (ref "U3") (pin "16") (pinfunction "ISET_16") (pintype "bidirectional"))
    )
    (net (code "37") (name "Net-(U3-TMR)") (class "Default")
      (node (ref "R12") (pin "1") (pinfunction "1_1") (pintype "passive"))
      (node (ref "U3") (pin "14") (pinfunction "TMR_14") (pintype "input"))
    )
    (net (code "38") (name "Net-(U3-~{CHG})") (class "Default")
      (node (ref "D4") (pin "C") (pinfunction "C_C") (pintype "passive"))
      (node (ref "U3") (pin "9") (pinfunction "~{CHG}_9") (pintype "output"))
    )
    (net (code "39") (name "Net-(U3-~{PGOOD})") (class "Default")
      (node (ref "D2") (pin "C") (pinfunction "C_C") (pintype "passive"))
      (node (ref "U3") (pin "7") (pinfunction "~{PGOOD}_7") (pintype "output"))
    )
    (net (code "40") (name "OLED_CS") (class "Default")
      (node (ref "JP6") (pin "5") (pinfunction "5_5") (pintype "passive"))
      (node (ref "JP8") (pin "4") (pinfunction "4_4") (pintype "passive"))
      (node (ref "PICAM_SHIELD") (pin "P1_24") (pinfunction "GPIO8/SPI0_CE0_P1_24") (pintype "bidirectional"))
    )
    (net (code "41") (name "OLED_DC") (class "Default")
      (node (ref "JP6") (pin "16") (pinfunction "16_16") (pintype "passive"))
      (node (ref "JP8") (pin "6") (pinfunction "6_6") (pintype "passive"))
      (node (ref "PICAM_SHIELD") (pin "P1_22") (pinfunction "GPIO25_P1_22") (pintype "bidirectional"))
    )
    (net (code "42") (name "OLED_RST") (class "Default")
      (node (ref "JP6") (pin "15") (pinfunction "15_15") (pintype "passive"))
      (node (ref "JP8") (pin "5") (pinfunction "5_5") (pintype "passive"))
      (node (ref "PICAM_SHIELD") (pin "P1_18") (pinfunction "GPIO24_P1_18") (pintype "bidirectional"))
    )
    (net (code "43") (name "PIEZO") (class "Default")
      (node (ref "JP6") (pin "12") (pinfunction "12_12") (pintype "passive"))
      (node (ref "PICAM_SHIELD") (pin "P1_12") (pinfunction "PWM0/GPIO18_P1_12") (pintype "bidirectional"))
      (node (ref "SG1") (pin "P$1") (pinfunction "1_P$1") (pintype "passive"))
    )
    (net (code "44") (name "ROT_A") (class "Default")
      (node (ref "JP4") (pin "2") (pinfunction "2_2") (pintype "bidirectional"))
      (node (ref "JP6") (pin "9") (pinfunction "9_9") (pintype "passive"))
      (node (ref "PICAM_SHIELD") (pin "P1_8") (pinfunction "UART0_TXD/GPIO14_P1_8") (pintype "bidirectional"))
    )
    (net (code "45") (name "ROT_B") (class "Default")
      (node (ref "JP4") (pin "1") (pinfunction "1_1") (pintype "bidirectional"))
      (node (ref "JP6") (pin "10") (pinfunction "10_10") (pintype "passive"))
      (node (ref "PICAM_SHIELD") (pin "P1_10") (pinfunction "UART0_RXD/GPIO15_P1_10") (pintype "bidirectional"))
    )
    (net (code "46") (name "ROT_SW") (class "Default")
      (node (ref "JP4") (pin "3") (pinfunction "3_3") (pintype "bidirectional"))
      (node (ref "JP6") (pin "11") (pinfunction "11_11") (pintype "passive"))
      (node (ref "PICAM_SHIELD") (pin "P1_11") (pinfunction "UART0_RTS/GPIO17_P1_11") (pintype "bidirectional"))
    )
    (net (code "47") (name "SD_CS") (class "Default")
      (node (ref "JP6") (pin "4") (pinfunction "4_4") (pintype "passive"))
      (node (ref "JP8") (pin "3") (pinfunction "3_3") (pintype "passive"))
      (node (ref "PICAM_SHIELD") (pin "P1_26") (pinfunction "GPIO7/SPI0_CE1_P1_26") (pintype "bidirectional"))
    )
    (net (code "48") (name "SHUTDOWN") (class "Default")
      (node (ref "JP6") (pin "3") (pinfunction "3_3") (pintype "passive"))
      (node (ref "PICAM_SHIELD") (pin "P1_7") (pinfunction "GPIO4/GPCLK0_P1_7") (pintype "bidirectional"))
      (node (ref "SJ5") (pin "3") (pinfunction "3_3") (pintype "passive"))
    )
    (net (code "49") (name "SPI_MISO") (class "Default")
      (node (ref "JP6") (pin "6") (pinfunction "6_6") (pintype "passive"))
      (node (ref "JP8") (pin "9") (pinfunction "9_9") (pintype "passive"))
      (node (ref "PICAM_SHIELD") (pin "P1_21") (pinfunction "GPIO9/SPI0_MISO_P1_21") (pintype "bidirectional"))
    )
    (net (code "50") (name "SPI_MOSI") (class "Default")
      (node (ref "JP6") (pin "7") (pinfunction "7_7") (pintype "passive"))
      (node (ref "JP8") (pin "8") (pinfunction "8_8") (pintype "passive"))
      (node (ref "PICAM_SHIELD") (pin "P1_19") (pinfunction "GPIO10/SPI0_MOSI_P1_19") (pintype "bidirectional"))
    )
    (net (code "51") (name "SPI_SCLK") (class "Default")
      (node (ref "JP6") (pin "8") (pinfunction "8_8") (pintype "passive"))
      (node (ref "JP8") (pin "7") (pinfunction "7_7") (pintype "passive"))
      (node (ref "PICAM_SHIELD") (pin "P1_23") (pinfunction "GPIO11/SPI0_SLCK_P1_23") (pintype "bidirectional"))
    )
    (net (code "52") (name "TS") (class "Default")
      (node (ref "R28") (pin "2") (pinfunction "2_2") (pintype "passive"))
      (node (ref "R29") (pin "1") (pinfunction "1_1") (pintype "passive"))
      (node (ref "SJ1") (pin "1") (pinfunction "1_1") (pintype "passive"))
      (node (ref "TEMP") (pin "1") (pinfunction "TP_1") (pintype "passive"))
      (node (ref "U3") (pin "1") (pinfunction "TS_1") (pintype "bidirectional"))
    )
    (net (code "53") (name "TS_GAUGE") (class "Default")
      (node (ref "R20") (pin "1") (pinfunction "1_1") (pintype "passive"))
      (node (ref "R21") (pin "1") (pinfunction "1_1") (pintype "passive"))
      (node (ref "SJ1") (pin "2") (pinfunction "2_2") (pintype "passive"))
    )
    (net (code "54") (name "VBAT") (class "Default")
      (node (ref "C13") (pin "1") (pinfunction "1_1") (pintype "passive"))
      (node (ref "C19") (pin "1") (pinfunction "1_1") (pintype "passive"))
      (node (ref "JP1") (pin "1") (pinfunction "2_1") (pintype "passive"))
      (node (ref "U2") (pin "3") (pinfunction "REGIN_3") (pintype "power_in"))
      (node (ref "U2") (pin "4") (pinfunction "BAT_4") (pintype "input"))
      (node (ref "U3") (pin "2") (pinfunction "BAT_2_2") (pintype "bidirectional"))
      (node (ref "U3") (pin "3") (pinfunction "BAT_3") (pintype "bidirectional"))
    )
    (net (code "55") (name "VBAT_NEG") (class "Default")
      (node (ref "JP1") (pin "2") (pinfunction "1_2") (pintype "passive"))
      (node (ref "R14") (pin "2") (pinfunction "2_2") (pintype "passive"))
      (node (ref "R15") (pin "1") (pinfunction "1_1") (pintype "passive"))
    )
    (net (code "56") (name "VBAT_SW") (class "Default")
      (node (ref "C1") (pin "1") (pinfunction "1_1") (pintype "passive"))
      (node (ref "C5") (pin "1") (pinfunction "1_1") (pintype "passive"))
      (node (ref "L1") (pin "P$1") (pinfunction "1_P$1") (pintype "passive"))
      (node (ref "L1") (pin "P$2") (pinfunction "1_P$2") (pintype "passive"))
      (node (ref "Q1") (pin "5") (pinfunction "P-D2_5") (pintype "passive"))
      (node (ref "Q1") (pin "6") (pinfunction "P-D2_6") (pintype "passive"))
      (node (ref "R2") (pin "2") (pinfunction "2_2") (pintype "passive"))
      (node (ref "R9") (pin "1") (pinfunction "1_1") (pintype "passive"))
      (node (ref "U1") (pin "11") (pinfunction "EN_11") (pintype "input"))
      (node (ref "U1") (pin "8") (pinfunction "VBAT_8") (pintype "input"))
    )
    (net (code "57") (name "unconnected-(U1-FB-Pad14)") (class "Default")
      (node (ref "U1") (pin "14") (pinfunction "FB_14") (pintype "input"))
    )
    (net (code "58") (name "unconnected-(U1-NC-Pad2)") (class "Default")
      (node (ref "U1") (pin "2") (pinfunction "NC_2") (pintype "no_connect"))
    )
  )
)
